# FX_I2C_Proto_Shield_v1_0.net
KiCad netlist of a schematic drawn in EAGLE
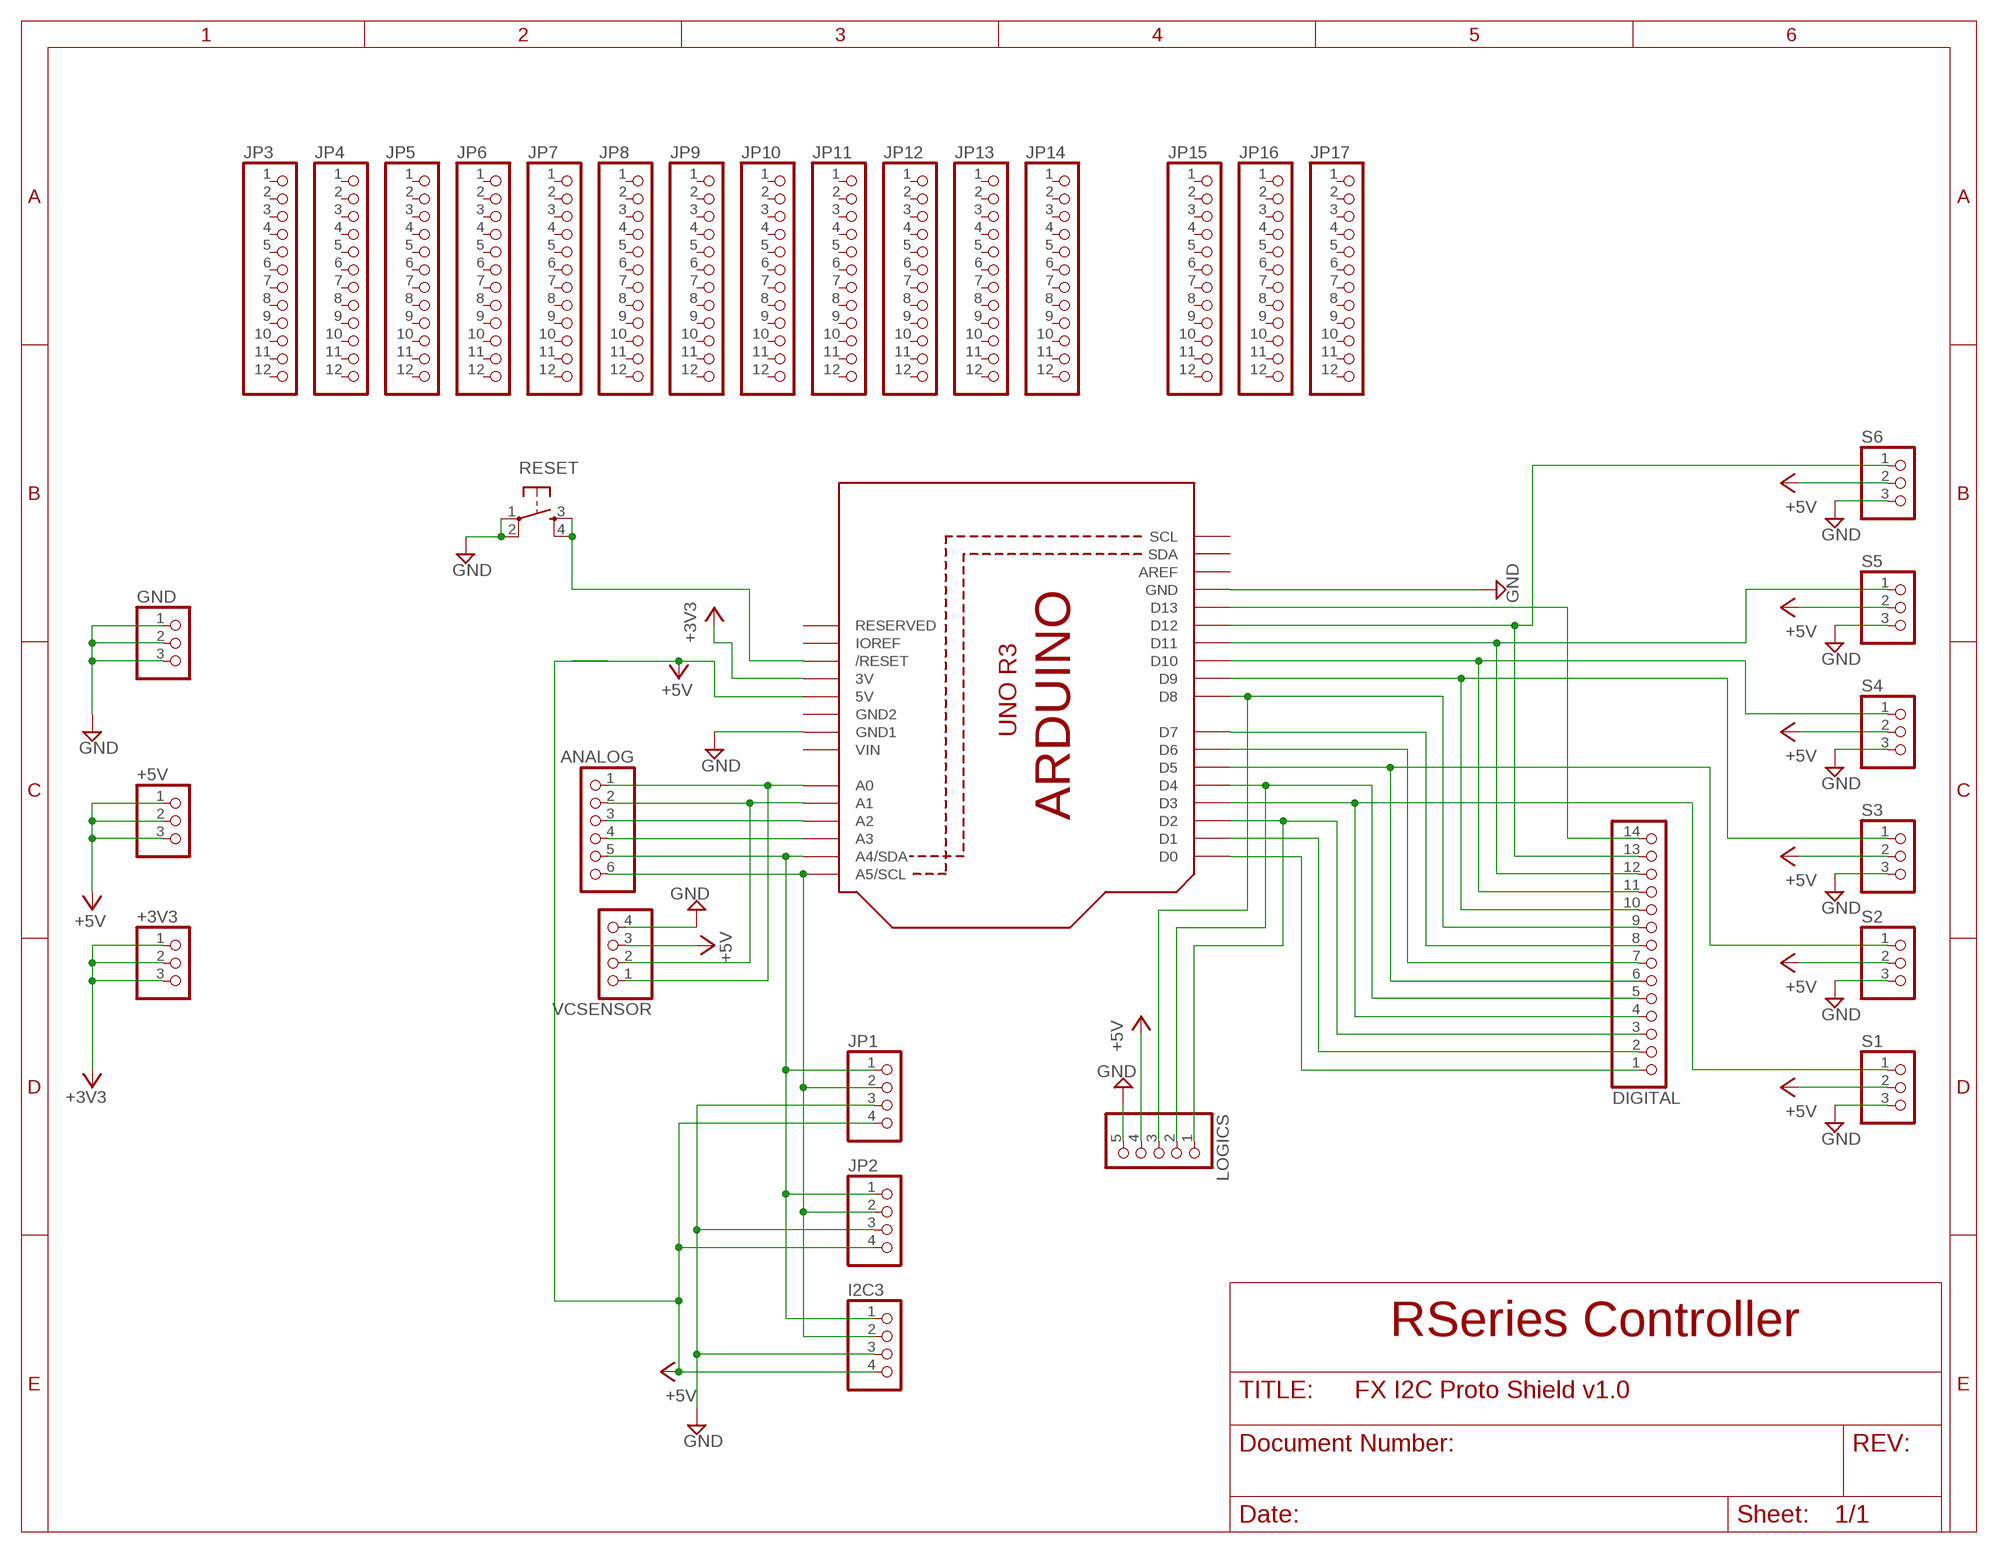
[diagram p0: schematic, sheet 1]

(export (version "E")
  (design (tool "Eeschema 10.0.6"))
  (components
    (comp (ref "+3V3")
      (value "PINHD-1X3CB")
      (footprint "eagle-import:1X03-CLEANBIG")
      (libsource (lib "eagle-import") (part "PINHD-1X3CB"))
    )
    (comp (ref "+5V")
      (value "PINHD-1X3CB")
      (footprint "eagle-import:1X03-CLEANBIG")
      (libsource (lib "eagle-import") (part "PINHD-1X3CB"))
    )
    (comp (ref "ANALOG")
      (value "PINHD-1X6B")
      (footprint "eagle-import:1X06-BIG")
      (libsource (lib "eagle-import") (part "PINHD-1X6B"))
    )
    (comp (ref "DIGITAL")
      (value "PINHD-1X14-CB")
      (footprint "eagle-import:1X14-CB")
      (libsource (lib "eagle-import") (part "PINHD-1X14-CB"))
    )
    (comp (ref "GND")
      (value "PINHD-1X3CB")
      (footprint "eagle-import:1X03-CLEANBIG")
      (libsource (lib "eagle-import") (part "PINHD-1X3CB"))
    )
    (comp (ref "I2C3")
      (value "PINHD-1X4")
      (footprint "eagle-import:1X04")
      (libsource (lib "eagle-import") (part "PINHD-1X4"))
    )
    (comp (ref "JP1")
      (value "PINHD-1X4")
      (footprint "eagle-import:1X04")
      (libsource (lib "eagle-import") (part "PINHD-1X4"))
    )
    (comp (ref "JP2")
      (value "PINHD-1X4")
      (footprint "eagle-import:1X04")
      (libsource (lib "eagle-import") (part "PINHD-1X4"))
    )
    (comp (ref "JP3")
      (value "PINHD-1X12-CB")
      (footprint "eagle-import:1X12-CB")
      (libsource (lib "eagle-import") (part "PINHD-1X12-CB"))
    )
    (comp (ref "JP4")
      (value "PINHD-1X12-CB")
      (footprint "eagle-import:1X12-CB")
      (libsource (lib "eagle-import") (part "PINHD-1X12-CB"))
    )
    (comp (ref "JP5")
      (value "PINHD-1X12-CB")
      (footprint "eagle-import:1X12-CB")
      (libsource (lib "eagle-import") (part "PINHD-1X12-CB"))
    )
    (comp (ref "JP6")
      (value "PINHD-1X12-CB")
      (footprint "eagle-import:1X12-CB")
      (libsource (lib "eagle-import") (part "PINHD-1X12-CB"))
    )
    (comp (ref "JP7")
      (value "PINHD-1X12-CB")
      (footprint "eagle-import:1X12-CB")
      (libsource (lib "eagle-import") (part "PINHD-1X12-CB"))
    )
    (comp (ref "JP8")
      (value "PINHD-1X12-CB")
      (footprint "eagle-import:1X12-CB")
      (libsource (lib "eagle-import") (part "PINHD-1X12-CB"))
    )
    (comp (ref "JP9")
      (value "PINHD-1X12-CB")
      (footprint "eagle-import:1X12-CB")
      (libsource (lib "eagle-import") (part "PINHD-1X12-CB"))
    )
    (comp (ref "JP10")
      (value "PINHD-1X12-CB")
      (footprint "eagle-import:1X12-CB")
      (libsource (lib "eagle-import") (part "PINHD-1X12-CB"))
    )
    (comp (ref "JP11")
      (value "PINHD-1X12-CB")
      (footprint "eagle-import:1X12-CB")
      (libsource (lib "eagle-import") (part "PINHD-1X12-CB"))
    )
    (comp (ref "JP12")
      (value "PINHD-1X12-CB")
      (footprint "eagle-import:1X12-CB")
      (libsource (lib "eagle-import") (part "PINHD-1X12-CB"))
    )
    (comp (ref "JP13")
      (value "PINHD-1X12-CB")
      (footprint "eagle-import:1X12-CB")
      (libsource (lib "eagle-import") (part "PINHD-1X12-CB"))
    )
    (comp (ref "JP14")
      (value "PINHD-1X12-CB")
      (footprint "eagle-import:1X12-CB")
      (libsource (lib "eagle-import") (part "PINHD-1X12-CB"))
    )
    (comp (ref "JP15")
      (value "PINHD-1X12-CB")
      (footprint "eagle-import:1X12-CB")
      (libsource (lib "eagle-import") (part "PINHD-1X12-CB"))
    )
    (comp (ref "JP16")
      (value "PINHD-1X12-CB")
      (footprint "eagle-import:1X12-CB")
      (libsource (lib "eagle-import") (part "PINHD-1X12-CB"))
    )
    (comp (ref "JP17")
      (value "PINHD-1X12-CB")
      (footprint "eagle-import:1X12-CB")
      (libsource (lib "eagle-import") (part "PINHD-1X12-CB"))
    )
    (comp (ref "LOGICS")
      (value "PINHD-1X5")
      (footprint "eagle-import:1X05")
      (libsource (lib "eagle-import") (part "PINHD-1X5"))
    )
    (comp (ref "RESET")
      (value "TAC_SWITCHPTH")
      (footprint "eagle-import:TACTILE-PTH")
      (libsource (lib "eagle-import") (part "TAC_SWITCHPTH"))
    )
    (comp (ref "S1")
      (value "PINHD-1X3")
      (footprint "eagle-import:1X03")
      (libsource (lib "eagle-import") (part "PINHD-1X3"))
    )
    (comp (ref "S2")
      (value "PINHD-1X3")
      (footprint "eagle-import:1X03")
      (libsource (lib "eagle-import") (part "PINHD-1X3"))
    )
    (comp (ref "S3")
      (value "PINHD-1X3")
      (footprint "eagle-import:1X03")
      (libsource (lib "eagle-import") (part "PINHD-1X3"))
    )
    (comp (ref "S4")
      (value "PINHD-1X3")
      (footprint "eagle-import:1X03")
      (libsource (lib "eagle-import") (part "PINHD-1X3"))
    )
    (comp (ref "S5")
      (value "PINHD-1X3")
      (footprint "eagle-import:1X03")
      (libsource (lib "eagle-import") (part "PINHD-1X3"))
    )
    (comp (ref "S6")
      (value "PINHD-1X3")
      (footprint "eagle-import:1X03")
      (libsource (lib "eagle-import") (part "PINHD-1X3"))
    )
    (comp (ref "U1")
      (value "ARDUINOR3-DIMENSION")
      (footprint "eagle-import:ARDUINOR3")
      (libsource (lib "eagle-import") (part "ARDUINOR3-DIMENSION"))
    )
    (comp (ref "VCSENSOR")
      (value "PINHD-1X4")
      (footprint "eagle-import:1X04")
      (libsource (lib "eagle-import") (part "PINHD-1X4"))
    )
  )
  (nets
    (net (code "1") (name "+3V3") (class "Default")
      (node (ref "+3V3") (pin "1") (pinfunction "1_1") (pintype "passive"))
      (node (ref "+3V3") (pin "2") (pinfunction "2_2") (pintype "passive"))
      (node (ref "+3V3") (pin "3") (pinfunction "3_3") (pintype "passive"))
      (node (ref "U1") (pin "3V") (pinfunction "3V_3V") (pintype "power_in"))
    )
    (net (code "2") (name "+5V") (class "Default")
      (node (ref "+5V") (pin "1") (pinfunction "1_1") (pintype "passive"))
      (node (ref "+5V") (pin "2") (pinfunction "2_2") (pintype "passive"))
      (node (ref "+5V") (pin "3") (pinfunction "3_3") (pintype "passive"))
      (node (ref "I2C3") (pin "4") (pinfunction "4_4") (pintype "passive"))
      (node (ref "JP1") (pin "4") (pinfunction "4_4") (pintype "passive"))
      (node (ref "JP2") (pin "4") (pinfunction "4_4") (pintype "passive"))
      (node (ref "LOGICS") (pin "4") (pinfunction "4_4") (pintype "passive"))
      (node (ref "S1") (pin "2") (pinfunction "2_2") (pintype "passive"))
      (node (ref "S2") (pin "2") (pinfunction "2_2") (pintype "passive"))
      (node (ref "S3") (pin "2") (pinfunction "2_2") (pintype "passive"))
      (node (ref "S4") (pin "2") (pinfunction "2_2") (pintype "passive"))
      (node (ref "S5") (pin "2") (pinfunction "2_2") (pintype "passive"))
      (node (ref "S6") (pin "2") (pinfunction "2_2") (pintype "passive"))
      (node (ref "U1") (pin "5V") (pinfunction "5V_5V") (pintype "power_in"))
      (node (ref "VCSENSOR") (pin "3") (pinfunction "3_3") (pintype "passive"))
    )
    (net (code "3") (name "/GND2") (class "Default")
      (node (ref "U1") (pin "GND2") (pinfunction "GND2_GND2") (pintype "power_in"))
    )
    (net (code "4") (name "/VIN") (class "Default")
      (node (ref "U1") (pin "VIN") (pinfunction "VIN_VIN") (pintype "power_in"))
    )
    (net (code "5") (name "GND") (class "Default")
      (node (ref "GND") (pin "1") (pinfunction "1_1") (pintype "passive"))
      (node (ref "GND") (pin "2") (pinfunction "2_2") (pintype "passive"))
      (node (ref "GND") (pin "3") (pinfunction "3_3") (pintype "passive"))
      (node (ref "I2C3") (pin "3") (pinfunction "3_3") (pintype "passive"))
      (node (ref "JP1") (pin "3") (pinfunction "3_3") (pintype "passive"))
      (node (ref "JP2") (pin "3") (pinfunction "3_3") (pintype "passive"))
      (node (ref "LOGICS") (pin "5") (pinfunction "5_5") (pintype "passive"))
      (node (ref "RESET") (pin "1") (pinfunction "1_1") (pintype "passive"))
      (node (ref "RESET") (pin "2") (pinfunction "2_2") (pintype "passive"))
      (node (ref "S1") (pin "3") (pinfunction "3_3") (pintype "passive"))
      (node (ref "S2") (pin "3") (pinfunction "3_3") (pintype "passive"))
      (node (ref "S3") (pin "3") (pinfunction "3_3") (pintype "passive"))
      (node (ref "S4") (pin "3") (pinfunction "3_3") (pintype "passive"))
      (node (ref "S5") (pin "3") (pinfunction "3_3") (pintype "passive"))
      (node (ref "S6") (pin "3") (pinfunction "3_3") (pintype "passive"))
      (node (ref "U1") (pin "GND") (pinfunction "GND_GND") (pintype "power_in"))
      (node (ref "U1") (pin "GND1") (pinfunction "GND1_GND1") (pintype "power_in"))
      (node (ref "VCSENSOR") (pin "4") (pinfunction "4_4") (pintype "passive"))
    )
    (net (code "6") (name "Net-(ANALOG-Pad1)") (class "Default")
      (node (ref "ANALOG") (pin "1") (pinfunction "1_1") (pintype "passive"))
      (node (ref "U1") (pin "A0") (pinfunction "A0_A0") (pintype "bidirectional"))
      (node (ref "VCSENSOR") (pin "1") (pinfunction "1_1") (pintype "passive"))
    )
    (net (code "7") (name "Net-(ANALOG-Pad2)") (class "Default")
      (node (ref "ANALOG") (pin "2") (pinfunction "2_2") (pintype "passive"))
      (node (ref "U1") (pin "A1") (pinfunction "A1_A1") (pintype "bidirectional"))
      (node (ref "VCSENSOR") (pin "2") (pinfunction "2_2") (pintype "passive"))
    )
    (net (code "8") (name "Net-(ANALOG-Pad3)") (class "Default")
      (node (ref "ANALOG") (pin "3") (pinfunction "3_3") (pintype "passive"))
      (node (ref "U1") (pin "A2") (pinfunction "A2_A2") (pintype "bidirectional"))
    )
    (net (code "9") (name "Net-(ANALOG-Pad4)") (class "Default")
      (node (ref "ANALOG") (pin "4") (pinfunction "4_4") (pintype "passive"))
      (node (ref "U1") (pin "A3") (pinfunction "A3_A3") (pintype "bidirectional"))
    )
    (net (code "10") (name "Net-(DIGITAL-Pad1)") (class "Default")
      (node (ref "DIGITAL") (pin "1") (pinfunction "1_1") (pintype "passive"))
      (node (ref "U1") (pin "D0") (pinfunction "D0_D0") (pintype "bidirectional"))
    )
    (net (code "11") (name "Net-(DIGITAL-Pad2)") (class "Default")
      (node (ref "DIGITAL") (pin "2") (pinfunction "2_2") (pintype "passive"))
      (node (ref "U1") (pin "D1") (pinfunction "D1_D1") (pintype "bidirectional"))
    )
    (net (code "12") (name "Net-(DIGITAL-Pad3)") (class "Default")
      (node (ref "DIGITAL") (pin "3") (pinfunction "3_3") (pintype "passive"))
      (node (ref "LOGICS") (pin "1") (pinfunction "1_1") (pintype "passive"))
      (node (ref "U1") (pin "D2") (pinfunction "D2_D2") (pintype "bidirectional"))
    )
    (net (code "13") (name "Net-(DIGITAL-Pad4)") (class "Default")
      (node (ref "DIGITAL") (pin "4") (pinfunction "4_4") (pintype "passive"))
      (node (ref "S1") (pin "1") (pinfunction "1_1") (pintype "passive"))
      (node (ref "U1") (pin "D3") (pinfunction "D3_D3") (pintype "bidirectional"))
    )
    (net (code "14") (name "Net-(DIGITAL-Pad5)") (class "Default")
      (node (ref "DIGITAL") (pin "5") (pinfunction "5_5") (pintype "passive"))
      (node (ref "LOGICS") (pin "2") (pinfunction "2_2") (pintype "passive"))
      (node (ref "U1") (pin "D4") (pinfunction "D4_D4") (pintype "bidirectional"))
    )
    (net (code "15") (name "Net-(DIGITAL-Pad6)") (class "Default")
      (node (ref "DIGITAL") (pin "6") (pinfunction "6_6") (pintype "passive"))
      (node (ref "S2") (pin "1") (pinfunction "1_1") (pintype "passive"))
      (node (ref "U1") (pin "D5") (pinfunction "D5_D5") (pintype "bidirectional"))
    )
    (net (code "16") (name "Net-(DIGITAL-Pad7)") (class "Default")
      (node (ref "DIGITAL") (pin "7") (pinfunction "7_7") (pintype "passive"))
      (node (ref "U1") (pin "D6") (pinfunction "D6_D6") (pintype "bidirectional"))
    )
    (net (code "17") (name "Net-(DIGITAL-Pad8)") (class "Default")
      (node (ref "DIGITAL") (pin "8") (pinfunction "8_8") (pintype "passive"))
      (node (ref "U1") (pin "D7") (pinfunction "D7_D7") (pintype "bidirectional"))
    )
    (net (code "18") (name "Net-(DIGITAL-Pad9)") (class "Default")
      (node (ref "DIGITAL") (pin "9") (pinfunction "9_9") (pintype "passive"))
      (node (ref "LOGICS") (pin "3") (pinfunction "3_3") (pintype "passive"))
      (node (ref "U1") (pin "D8") (pinfunction "D8_D8") (pintype "bidirectional"))
    )
    (net (code "19") (name "Net-(DIGITAL-Pad10)") (class "Default")
      (node (ref "DIGITAL") (pin "10") (pinfunction "10_10") (pintype "passive"))
      (node (ref "S3") (pin "1") (pinfunction "1_1") (pintype "passive"))
      (node (ref "U1") (pin "D9") (pinfunction "D9_D9") (pintype "bidirectional"))
    )
    (net (code "20") (name "Net-(DIGITAL-Pad11)") (class "Default")
      (node (ref "DIGITAL") (pin "11") (pinfunction "11_11") (pintype "passive"))
      (node (ref "S4") (pin "1") (pinfunction "1_1") (pintype "passive"))
      (node (ref "U1") (pin "D10") (pinfunction "D10_D10") (pintype "bidirectional"))
    )
    (net (code "21") (name "Net-(DIGITAL-Pad12)") (class "Default")
      (node (ref "DIGITAL") (pin "12") (pinfunction "12_12") (pintype "passive"))
      (node (ref "S5") (pin "1") (pinfunction "1_1") (pintype "passive"))
      (node (ref "U1") (pin "D11") (pinfunction "D11_D11") (pintype "bidirectional"))
    )
    (net (code "22") (name "Net-(DIGITAL-Pad13)") (class "Default")
      (node (ref "DIGITAL") (pin "13") (pinfunction "13_13") (pintype "passive"))
      (node (ref "S6") (pin "1") (pinfunction "1_1") (pintype "passive"))
      (node (ref "U1") (pin "D12") (pinfunction "D12_D12") (pintype "bidirectional"))
    )
    (net (code "23") (name "Net-(DIGITAL-Pad14)") (class "Default")
      (node (ref "DIGITAL") (pin "14") (pinfunction "14_14") (pintype "passive"))
      (node (ref "U1") (pin "D13") (pinfunction "D13_D13") (pintype "bidirectional"))
    )
    (net (code "24") (name "Net-(U1-A4{slash}SDA)") (class "Default")
      (node (ref "ANALOG") (pin "5") (pinfunction "5_5") (pintype "passive"))
      (node (ref "I2C3") (pin "1") (pinfunction "1_1") (pintype "passive"))
      (node (ref "JP1") (pin "1") (pinfunction "1_1") (pintype "passive"))
      (node (ref "JP2") (pin "1") (pinfunction "1_1") (pintype "passive"))
      (node (ref "U1") (pin "A4") (pinfunction "A4/SDA_A4") (pintype "bidirectional"))
    )
    (net (code "25") (name "Net-(U1-A5{slash}SCL)") (class "Default")
      (node (ref "ANALOG") (pin "6") (pinfunction "6_6") (pintype "passive"))
      (node (ref "I2C3") (pin "2") (pinfunction "2_2") (pintype "passive"))
      (node (ref "JP1") (pin "2") (pinfunction "2_2") (pintype "passive"))
      (node (ref "JP2") (pin "2") (pinfunction "2_2") (pintype "passive"))
      (node (ref "U1") (pin "A5") (pinfunction "A5/SCL_A5") (pintype "bidirectional"))
    )
    (net (code "26") (name "Net-(U1-{slash}RESET)") (class "Default")
      (node (ref "RESET") (pin "3") (pinfunction "3_3") (pintype "passive"))
      (node (ref "RESET") (pin "4") (pinfunction "4_4") (pintype "passive"))
      (node (ref "U1") (pin "RESET") (pinfunction "/RESET_RESET") (pintype "bidirectional"))
    )
    (net (code "27") (name "unconnected-(JP3-Pad1)") (class "Default")
      (node (ref "JP3") (pin "1") (pinfunction "1_1") (pintype "passive"))
    )
    (net (code "28") (name "unconnected-(JP3-Pad2)") (class "Default")
      (node (ref "JP3") (pin "2") (pinfunction "2_2") (pintype "passive"))
    )
    (net (code "29") (name "unconnected-(JP3-Pad3)") (class "Default")
      (node (ref "JP3") (pin "3") (pinfunction "3_3") (pintype "passive"))
    )
    (net (code "30") (name "unconnected-(JP3-Pad4)") (class "Default")
      (node (ref "JP3") (pin "4") (pinfunction "4_4") (pintype "passive"))
    )
    (net (code "31") (name "unconnected-(JP3-Pad5)") (class "Default")
      (node (ref "JP3") (pin "5") (pinfunction "5_5") (pintype "passive"))
    )
    (net (code "32") (name "unconnected-(JP3-Pad6)") (class "Default")
      (node (ref "JP3") (pin "6") (pinfunction "6_6") (pintype "passive"))
    )
    (net (code "33") (name "unconnected-(JP3-Pad7)") (class "Default")
      (node (ref "JP3") (pin "7") (pinfunction "7_7") (pintype "passive"))
    )
    (net (code "34") (name "unconnected-(JP3-Pad8)") (class "Default")
      (node (ref "JP3") (pin "8") (pinfunction "8_8") (pintype "passive"))
    )
    (net (code "35") (name "unconnected-(JP3-Pad9)") (class "Default")
      (node (ref "JP3") (pin "9") (pinfunction "9_9") (pintype "passive"))
    )
    (net (code "36") (name "unconnected-(JP3-Pad10)") (class "Default")
      (node (ref "JP3") (pin "10") (pinfunction "10_10") (pintype "passive"))
    )
    (net (code "37") (name "unconnected-(JP3-Pad11)") (class "Default")
      (node (ref "JP3") (pin "11") (pinfunction "11_11") (pintype "passive"))
    )
    (net (code "38") (name "unconnected-(JP3-Pad12)") (class "Default")
      (node (ref "JP3") (pin "12") (pinfunction "12_12") (pintype "passive"))
    )
    (net (code "39") (name "unconnected-(JP4-Pad1)") (class "Default")
      (node (ref "JP4") (pin "1") (pinfunction "1_1") (pintype "passive"))
    )
    (net (code "40") (name "unconnected-(JP4-Pad2)") (class "Default")
      (node (ref "JP4") (pin "2") (pinfunction "2_2") (pintype "passive"))
    )
    (net (code "41") (name "unconnected-(JP4-Pad3)") (class "Default")
      (node (ref "JP4") (pin "3") (pinfunction "3_3") (pintype "passive"))
    )
    (net (code "42") (name "unconnected-(JP4-Pad4)") (class "Default")
      (node (ref "JP4") (pin "4") (pinfunction "4_4") (pintype "passive"))
    )
    (net (code "43") (name "unconnected-(JP4-Pad5)") (class "Default")
      (node (ref "JP4") (pin "5") (pinfunction "5_5") (pintype "passive"))
    )
    (net (code "44") (name "unconnected-(JP4-Pad6)") (class "Default")
      (node (ref "JP4") (pin "6") (pinfunction "6_6") (pintype "passive"))
    )
    (net (code "45") (name "unconnected-(JP4-Pad7)") (class "Default")
      (node (ref "JP4") (pin "7") (pinfunction "7_7") (pintype "passive"))
    )
    (net (code "46") (name "unconnected-(JP4-Pad8)") (class "Default")
      (node (ref "JP4") (pin "8") (pinfunction "8_8") (pintype "passive"))
    )
    (net (code "47") (name "unconnected-(JP4-Pad9)") (class "Default")
      (node (ref "JP4") (pin "9") (pinfunction "9_9") (pintype "passive"))
    )
    (net (code "48") (name "unconnected-(JP4-Pad10)") (class "Default")
      (node (ref "JP4") (pin "10") (pinfunction "10_10") (pintype "passive"))
    )
    (net (code "49") (name "unconnected-(JP4-Pad11)") (class "Default")
      (node (ref "JP4") (pin "11") (pinfunction "11_11") (pintype "passive"))
    )
    (net (code "50") (name "unconnected-(JP4-Pad12)") (class "Default")
      (node (ref "JP4") (pin "12") (pinfunction "12_12") (pintype "passive"))
    )
    (net (code "51") (name "unconnected-(JP5-Pad1)") (class "Default")
      (node (ref "JP5") (pin "1") (pinfunction "1_1") (pintype "passive"))
    )
    (net (code "52") (name "unconnected-(JP5-Pad2)") (class "Default")
      (node (ref "JP5") (pin "2") (pinfunction "2_2") (pintype "passive"))
    )
    (net (code "53") (name "unconnected-(JP5-Pad3)") (class "Default")
      (node (ref "JP5") (pin "3") (pinfunction "3_3") (pintype "passive"))
    )
    (net (code "54") (name "unconnected-(JP5-Pad4)") (class "Default")
      (node (ref "JP5") (pin "4") (pinfunction "4_4") (pintype "passive"))
    )
    (net (code "55") (name "unconnected-(JP5-Pad5)") (class "Default")
      (node (ref "JP5") (pin "5") (pinfunction "5_5") (pintype "passive"))
    )
    (net (code "56") (name "unconnected-(JP5-Pad6)") (class "Default")
      (node (ref "JP5") (pin "6") (pinfunction "6_6") (pintype "passive"))
    )
    (net (code "57") (name "unconnected-(JP5-Pad7)") (class "Default")
      (node (ref "JP5") (pin "7") (pinfunction "7_7") (pintype "passive"))
    )
    (net (code "58") (name "unconnected-(JP5-Pad8)") (class "Default")
      (node (ref "JP5") (pin "8") (pinfunction "8_8") (pintype "passive"))
    )
    (net (code "59") (name "unconnected-(JP5-Pad9)") (class "Default")
      (node (ref "JP5") (pin "9") (pinfunction "9_9") (pintype "passive"))
    )
    (net (code "60") (name "unconnected-(JP5-Pad10)") (class "Default")
      (node (ref "JP5") (pin "10") (pinfunction "10_10") (pintype "passive"))
    )
    (net (code "61") (name "unconnected-(JP5-Pad11)") (class "Default")
      (node (ref "JP5") (pin "11") (pinfunction "11_11") (pintype "passive"))
    )
    (net (code "62") (name "unconnected-(JP5-Pad12)") (class "Default")
      (node (ref "JP5") (pin "12") (pinfunction "12_12") (pintype "passive"))
    )
    (net (code "63") (name "unconnected-(JP6-Pad1)") (class "Default")
      (node (ref "JP6") (pin "1") (pinfunction "1_1") (pintype "passive"))
    )
    (net (code "64") (name "unconnected-(JP6-Pad2)") (class "Default")
      (node (ref "JP6") (pin "2") (pinfunction "2_2") (pintype "passive"))
    )
    (net (code "65") (name "unconnected-(JP6-Pad3)") (class "Default")
      (node (ref "JP6") (pin "3") (pinfunction "3_3") (pintype "passive"))
    )
    (net (code "66") (name "unconnected-(JP6-Pad4)") (class "Default")
      (node (ref "JP6") (pin "4") (pinfunction "4_4") (pintype "passive"))
    )
    (net (code "67") (name "unconnected-(JP6-Pad5)") (class "Default")
      (node (ref "JP6") (pin "5") (pinfunction "5_5") (pintype "passive"))
    )
    (net (code "68") (name "unconnected-(JP6-Pad6)") (class "Default")
      (node (ref "JP6") (pin "6") (pinfunction "6_6") (pintype "passive"))
    )
    (net (code "69") (name "unconnected-(JP6-Pad7)") (class "Default")
      (node (ref "JP6") (pin "7") (pinfunction "7_7") (pintype "passive"))
    )
    (net (code "70") (name "unconnected-(JP6-Pad8)") (class "Default")
      (node (ref "JP6") (pin "8") (pinfunction "8_8") (pintype "passive"))
    )
    (net (code "71") (name "unconnected-(JP6-Pad9)") (class "Default")
      (node (ref "JP6") (pin "9") (pinfunction "9_9") (pintype "passive"))
    )
    (net (code "72") (name "unconnected-(JP6-Pad10)") (class "Default")
      (node (ref "JP6") (pin "10") (pinfunction "10_10") (pintype "passive"))
    )
    (net (code "73") (name "unconnected-(JP6-Pad11)") (class "Default")
      (node (ref "JP6") (pin "11") (pinfunction "11_11") (pintype "passive"))
    )
    (net (code "74") (name "unconnected-(JP6-Pad12)") (class "Default")
      (node (ref "JP6") (pin "12") (pinfunction "12_12") (pintype "passive"))
    )
    (net (code "75") (name "unconnected-(JP7-Pad1)") (class "Default")
      (node (ref "JP7") (pin "1") (pinfunction "1_1") (pintype "passive"))
    )
    (net (code "76") (name "unconnected-(JP7-Pad2)") (class "Default")
      (node (ref "JP7") (pin "2") (pinfunction "2_2") (pintype "passive"))
    )
    (net (code "77") (name "unconnected-(JP7-Pad3)") (class "Default")
      (node (ref "JP7") (pin "3") (pinfunction "3_3") (pintype "passive"))
    )
    (net (code "78") (name "unconnected-(JP7-Pad4)") (class "Default")
      (node (ref "JP7") (pin "4") (pinfunction "4_4") (pintype "passive"))
    )
    (net (code "79") (name "unconnected-(JP7-Pad5)") (class "Default")
      (node (ref "JP7") (pin "5") (pinfunction "5_5") (pintype "passive"))
    )
    (net (code "80") (name "unconnected-(JP7-Pad6)") (class "Default")
      (node (ref "JP7") (pin "6") (pinfunction "6_6") (pintype "passive"))
    )
    (net (code "81") (name "unconnected-(JP7-Pad7)") (class "Default")
      (node (ref "JP7") (pin "7") (pinfunction "7_7") (pintype "passive"))
    )
    (net (code "82") (name "unconnected-(JP7-Pad8)") (class "Default")
      (node (ref "JP7") (pin "8") (pinfunction "8_8") (pintype "passive"))
    )
    (net (code "83") (name "unconnected-(JP7-Pad9)") (class "Default")
      (node (ref "JP7") (pin "9") (pinfunction "9_9") (pintype "passive"))
    )
    (net (code "84") (name "unconnected-(JP7-Pad10)") (class "Default")
      (node (ref "JP7") (pin "10") (pinfunction "10_10") (pintype "passive"))
    )
    (net (code "85") (name "unconnected-(JP7-Pad11)") (class "Default")
      (node (ref "JP7") (pin "11") (pinfunction "11_11") (pintype "passive"))
    )
    (net (code "86") (name "unconnected-(JP7-Pad12)") (class "Default")
      (node (ref "JP7") (pin "12") (pinfunction "12_12") (pintype "passive"))
    )
    (net (code "87") (name "unconnected-(JP8-Pad1)") (class "Default")
      (node (ref "JP8") (pin "1") (pinfunction "1_1") (pintype "passive"))
    )
    (net (code "88") (name "unconnected-(JP8-Pad2)") (class "Default")
      (node (ref "JP8") (pin "2") (pinfunction "2_2") (pintype "passive"))
    )
    (net (code "89") (name "unconnected-(JP8-Pad3)") (class "Default")
      (node (ref "JP8") (pin "3") (pinfunction "3_3") (pintype "passive"))
    )
    (net (code "90") (name "unconnected-(JP8-Pad4)") (class "Default")
      (node (ref "JP8") (pin "4") (pinfunction "4_4") (pintype "passive"))
    )
    (net (code "91") (name "unconnected-(JP8-Pad5)") (class "Default")
      (node (ref "JP8") (pin "5") (pinfunction "5_5") (pintype "passive"))
    )
    (net (code "92") (name "unconnected-(JP8-Pad6)") (class "Default")
      (node (ref "JP8") (pin "6") (pinfunction "6_6") (pintype "passive"))
    )
    (net (code "93") (name "unconnected-(JP8-Pad7)") (class "Default")
      (node (ref "JP8") (pin "7") (pinfunction "7_7") (pintype "passive"))
    )
    (net (code "94") (name "unconnected-(JP8-Pad8)") (class "Default")
      (node (ref "JP8") (pin "8") (pinfunction "8_8") (pintype "passive"))
    )
    (net (code "95") (name "unconnected-(JP8-Pad9)") (class "Default")
      (node (ref "JP8") (pin "9") (pinfunction "9_9") (pintype "passive"))
    )
    (net (code "96") (name "unconnected-(JP8-Pad10)") (class "Default")
      (node (ref "JP8") (pin "10") (pinfunction "10_10") (pintype "passive"))
    )
    (net (code "97") (name "unconnected-(JP8-Pad11)") (class "Default")
      (node (ref "JP8") (pin "11") (pinfunction "11_11") (pintype "passive"))
    )
    (net (code "98") (name "unconnected-(JP8-Pad12)") (class "Default")
      (node (ref "JP8") (pin "12") (pinfunction "12_12") (pintype "passive"))
    )
    (net (code "99") (name "unconnected-(JP9-Pad1)") (class "Default")
      (node (ref "JP9") (pin "1") (pinfunction "1_1") (pintype "passive"))
    )
    (net (code "100") (name "unconnected-(JP9-Pad2)") (class "Default")
      (node (ref "JP9") (pin "2") (pinfunction "2_2") (pintype "passive"))
    )
    (net (code "101") (name "unconnected-(JP9-Pad3)") (class "Default")
      (node (ref "JP9") (pin "3") (pinfunction "3_3") (pintype "passive"))
    )
    (net (code "102") (name "unconnected-(JP9-Pad4)") (class "Default")
      (node (ref "JP9") (pin "4") (pinfunction "4_4") (pintype "passive"))
    )
    (net (code "103") (name "unconnected-(JP9-Pad5)") (class "Default")
      (node (ref "JP9") (pin "5") (pinfunction "5_5") (pintype "passive"))
    )
    (net (code "104") (name "unconnected-(JP9-Pad6)") (class "Default")
      (node (ref "JP9") (pin "6") (pinfunction "6_6") (pintype "passive"))
    )
    (net (code "105") (name "unconnected-(JP9-Pad7)") (class "Default")
      (node (ref "JP9") (pin "7") (pinfunction "7_7") (pintype "passive"))
    )
    (net (code "106") (name "unconnected-(JP9-Pad8)") (class "Default")
      (node (ref "JP9") (pin "8") (pinfunction "8_8") (pintype "passive"))
    )
    (net (code "107") (name "unconnected-(JP9-Pad9)") (class "Default")
      (node (ref "JP9") (pin "9") (pinfunction "9_9") (pintype "passive"))
    )
    (net (code "108") (name "unconnected-(JP9-Pad10)") (class "Default")
      (node (ref "JP9") (pin "10") (pinfunction "10_10") (pintype "passive"))
    )
    (net (code "109") (name "unconnected-(JP9-Pad11)") (class "Default")
      (node (ref "JP9") (pin "11") (pinfunction "11_11") (pintype "passive"))
    )
    (net (code "110") (name "unconnected-(JP9-Pad12)") (class "Default")
      (node (ref "JP9") (pin "12") (pinfunction "12_12") (pintype "passive"))
    )
    (net (code "111") (name "unconnected-(JP10-Pad1)") (class "Default")
      (node (ref "JP10") (pin "1") (pinfunction "1_1") (pintype "passive"))
    )
    (net (code "112") (name "unconnected-(JP10-Pad2)") (class "Default")
      (node (ref "JP10") (pin "2") (pinfunction "2_2") (pintype "passive"))
    )
    (net (code "113") (name "unconnected-(JP10-Pad3)") (class "Default")
      (node (ref "JP10") (pin "3") (pinfunction "3_3") (pintype "passive"))
    )
    (net (code "114") (name "unconnected-(JP10-Pad4)") (class "Default")
      (node (ref "JP10") (pin "4") (pinfunction "4_4") (pintype "passive"))
    )
    (net (code "115") (name "unconnected-(JP10-Pad5)") (class "Default")
      (node (ref "JP10") (pin "5") (pinfunction "5_5") (pintype "passive"))
    )
    (net (code "116") (name "unconnected-(JP10-Pad6)") (class "Default")
      (node (ref "JP10") (pin "6") (pinfunction "6_6") (pintype "passive"))
    )
    (net (code "117") (name "unconnected-(JP10-Pad7)") (class "Default")
      (node (ref "JP10") (pin "7") (pinfunction "7_7") (pintype "passive"))
    )
    (net (code "118") (name "unconnected-(JP10-Pad8)") (class "Default")
      (node (ref "JP10") (pin "8") (pinfunction "8_8") (pintype "passive"))
    )
    (net (code "119") (name "unconnected-(JP10-Pad9)") (class "Default")
      (node (ref "JP10") (pin "9") (pinfunction "9_9") (pintype "passive"))
    )
    (net (code "120") (name "unconnected-(JP10-Pad10)") (class "Default")
      (node (ref "JP10") (pin "10") (pinfunction "10_10") (pintype "passive"))
    )
    (net (code "121") (name "unconnected-(JP10-Pad11)") (class "Default")
      (node (ref "JP10") (pin "11") (pinfunction "11_11") (pintype "passive"))
    )
    (net (code "122") (name "unconnected-(JP10-Pad12)") (class "Default")
      (node (ref "JP10") (pin "12") (pinfunction "12_12") (pintype "passive"))
    )
    (net (code "123") (name "unconnected-(JP11-Pad1)") (class "Default")
      (node (ref "JP11") (pin "1") (pinfunction "1_1") (pintype "passive"))
    )
    (net (code "124") (name "unconnected-(JP11-Pad2)") (class "Default")
      (node (ref "JP11") (pin "2") (pinfunction "2_2") (pintype "passive"))
    )
    (net (code "125") (name "unconnected-(JP11-Pad3)") (class "Default")
      (node (ref "JP11") (pin "3") (pinfunction "3_3") (pintype "passive"))
    )
    (net (code "126") (name "unconnected-(JP11-Pad4)") (class "Default")
      (node (ref "JP11") (pin "4") (pinfunction "4_4") (pintype "passive"))
    )
    (net (code "127") (name "unconnected-(JP11-Pad5)") (class "Default")
      (node (ref "JP11") (pin "5") (pinfunction "5_5") (pintype "passive"))
    )
    (net (code "128") (name "unconnected-(JP11-Pad6)") (class "Default")
      (node (ref "JP11") (pin "6") (pinfunction "6_6") (pintype "passive"))
    )
    (net (code "129") (name "unconnected-(JP11-Pad7)") (class "Default")
      (node (ref "JP11") (pin "7") (pinfunction "7_7") (pintype "passive"))
    )
    (net (code "130") (name "unconnected-(JP11-Pad8)") (class "Default")
      (node (ref "JP11") (pin "8") (pinfunction "8_8") (pintype "passive"))
    )
    (net (code "131") (name "unconnected-(JP11-Pad9)") (class "Default")
      (node (ref "JP11") (pin "9") (pinfunction "9_9") (pintype "passive"))
    )
    (net (code "132") (name "unconnected-(JP11-Pad10)") (class "Default")
      (node (ref "JP11") (pin "10") (pinfunction "10_10") (pintype "passive"))
    )
    (net (code "133") (name "unconnected-(JP11-Pad11)") (class "Default")
      (node (ref "JP11") (pin "11") (pinfunction "11_11") (pintype "passive"))
    )
    (net (code "134") (name "unconnected-(JP11-Pad12)") (class "Default")
      (node (ref "JP11") (pin "12") (pinfunction "12_12") (pintype "passive"))
    )
    (net (code "135") (name "unconnected-(JP12-Pad1)") (class "Default")
      (node (ref "JP12") (pin "1") (pinfunction "1_1") (pintype "passive"))
    )
    (net (code "136") (name "unconnected-(JP12-Pad2)") (class "Default")
      (node (ref "JP12") (pin "2") (pinfunction "2_2") (pintype "passive"))
    )
    (net (code "137") (name "unconnected-(JP12-Pad3)") (class "Default")
      (node (ref "JP12") (pin "3") (pinfunction "3_3") (pintype "passive"))
    )
    (net (code "138") (name "unconnected-(JP12-Pad4)") (class "Default")
      (node (ref "JP12") (pin "4") (pinfunction "4_4") (pintype "passive"))
    )
    (net (code "139") (name "unconnected-(JP12-Pad5)") (class "Default")
      (node (ref "JP12") (pin "5") (pinfunction "5_5") (pintype "passive"))
    )
    (net (code "140") (name "unconnected-(JP12-Pad6)") (class "Default")
      (node (ref "JP12") (pin "6") (pinfunction "6_6") (pintype "passive"))
    )
    (net (code "141") (name "unconnected-(JP12-Pad7)") (class "Default")
      (node (ref "JP12") (pin "7") (pinfunction "7_7") (pintype "passive"))
    )
    (net (code "142") (name "unconnected-(JP12-Pad8)") (class "Default")
      (node (ref "JP12") (pin "8") (pinfunction "8_8") (pintype "passive"))
    )
    (net (code "143") (name "unconnected-(JP12-Pad9)") (class "Default")
      (node (ref "JP12") (pin "9") (pinfunction "9_9") (pintype "passive"))
    )
    (net (code "144") (name "unconnected-(JP12-Pad10)") (class "Default")
      (node (ref "JP12") (pin "10") (pinfunction "10_10") (pintype "passive"))
    )
    (net (code "145") (name "unconnected-(JP12-Pad11)") (class "Default")
      (node (ref "JP12") (pin "11") (pinfunction "11_11") (pintype "passive"))
    )
    (net (code "146") (name "unconnected-(JP12-Pad12)") (class "Default")
      (node (ref "JP12") (pin "12") (pinfunction "12_12") (pintype "passive"))
    )
    (net (code "147") (name "unconnected-(JP13-Pad1)") (class "Default")
      (node (ref "JP13") (pin "1") (pinfunction "1_1") (pintype "passive"))
    )
    (net (code "148") (name "unconnected-(JP13-Pad2)") (class "Default")
      (node (ref "JP13") (pin "2") (pinfunction "2_2") (pintype "passive"))
    )
    (net (code "149") (name "unconnected-(JP13-Pad3)") (class "Default")
      (node (ref "JP13") (pin "3") (pinfunction "3_3") (pintype "passive"))
    )
    (net (code "150") (name "unconnected-(JP13-Pad4)") (class "Default")
      (node (ref "JP13") (pin "4") (pinfunction "4_4") (pintype "passive"))
    )
    (net (code "151") (name "unconnected-(JP13-Pad5)") (class "Default")
      (node (ref "JP13") (pin "5") (pinfunction "5_5") (pintype "passive"))
    )
    (net (code "152") (name "unconnected-(JP13-Pad6)") (class "Default")
      (node (ref "JP13") (pin "6") (pinfunction "6_6") (pintype "passive"))
    )
    (net (code "153") (name "unconnected-(JP13-Pad7)") (class "Default")
      (node (ref "JP13") (pin "7") (pinfunction "7_7") (pintype "passive"))
    )
    (net (code "154") (name "unconnected-(JP13-Pad8)") (class "Default")
      (node (ref "JP13") (pin "8") (pinfunction "8_8") (pintype "passive"))
    )
    (net (code "155") (name "unconnected-(JP13-Pad9)") (class "Default")
      (node (ref "JP13") (pin "9") (pinfunction "9_9") (pintype "passive"))
    )
    (net (code "156") (name "unconnected-(JP13-Pad10)") (class "Default")
      (node (ref "JP13") (pin "10") (pinfunction "10_10") (pintype "passive"))
    )
    (net (code "157") (name "unconnected-(JP13-Pad11)") (class "Default")
      (node (ref "JP13") (pin "11") (pinfunction "11_11") (pintype "passive"))
    )
    (net (code "158") (name "unconnected-(JP13-Pad12)") (class "Default")
      (node (ref "JP13") (pin "12") (pinfunction "12_12") (pintype "passive"))
    )
    (net (code "159") (name "unconnected-(JP14-Pad1)") (class "Default")
      (node (ref "JP14") (pin "1") (pinfunction "1_1") (pintype "passive"))
    )
    (net (code "160") (name "unconnected-(JP14-Pad2)") (class "Default")
      (node (ref "JP14") (pin "2") (pinfunction "2_2") (pintype "passive"))
    )
    (net (code "161") (name "unconnected-(JP14-Pad3)") (class "Default")
      (node (ref "JP14") (pin "3") (pinfunction "3_3") (pintype "passive"))
    )
    (net (code "162") (name "unconnected-(JP14-Pad4)") (class "Default")
      (node (ref "JP14") (pin "4") (pinfunction "4_4") (pintype "passive"))
    )
    (net (code "163") (name "unconnected-(JP14-Pad5)") (class "Default")
      (node (ref "JP14") (pin "5") (pinfunction "5_5") (pintype "passive"))
    )
    (net (code "164") (name "unconnected-(JP14-Pad6)") (class "Default")
      (node (ref "JP14") (pin "6") (pinfunction "6_6") (pintype "passive"))
    )
    (net (code "165") (name "unconnected-(JP14-Pad7)") (class "Default")
      (node (ref "JP14") (pin "7") (pinfunction "7_7") (pintype "passive"))
    )
    (net (code "166") (name "unconnected-(JP14-Pad8)") (class "Default")
      (node (ref "JP14") (pin "8") (pinfunction "8_8") (pintype "passive"))
    )
    (net (code "167") (name "unconnected-(JP14-Pad9)") (class "Default")
      (node (ref "JP14") (pin "9") (pinfunction "9_9") (pintype "passive"))
    )
    (net (code "168") (name "unconnected-(JP14-Pad10)") (class "Default")
      (node (ref "JP14") (pin "10") (pinfunction "10_10") (pintype "passive"))
    )
    (net (code "169") (name "unconnected-(JP14-Pad11)") (class "Default")
      (node (ref "JP14") (pin "11") (pinfunction "11_11") (pintype "passive"))
    )
    (net (code "170") (name "unconnected-(JP14-Pad12)") (class "Default")
      (node (ref "JP14") (pin "12") (pinfunction "12_12") (pintype "passive"))
    )
    (net (code "171") (name "unconnected-(JP15-Pad1)") (class "Default")
      (node (ref "JP15") (pin "1") (pinfunction "1_1") (pintype "passive"))
    )
    (net (code "172") (name "unconnected-(JP15-Pad2)") (class "Default")
      (node (ref "JP15") (pin "2") (pinfunction "2_2") (pintype "passive"))
    )
    (net (code "173") (name "unconnected-(JP15-Pad3)") (class "Default")
      (node (ref "JP15") (pin "3") (pinfunction "3_3") (pintype "passive"))
    )
    (net (code "174") (name "unconnected-(JP15-Pad4)") (class "Default")
      (node (ref "JP15") (pin "4") (pinfunction "4_4") (pintype "passive"))
    )
    (net (code "175") (name "unconnected-(JP15-Pad5)") (class "Default")
      (node (ref "JP15") (pin "5") (pinfunction "5_5") (pintype "passive"))
    )
    (net (code "176") (name "unconnected-(JP15-Pad6)") (class "Default")
      (node (ref "JP15") (pin "6") (pinfunction "6_6") (pintype "passive"))
    )
    (net (code "177") (name "unconnected-(JP15-Pad7)") (class "Default")
      (node (ref "JP15") (pin "7") (pinfunction "7_7") (pintype "passive"))
    )
    (net (code "178") (name "unconnected-(JP15-Pad8)") (class "Default")
      (node (ref "JP15") (pin "8") (pinfunction "8_8") (pintype "passive"))
    )
    (net (code "179") (name "unconnected-(JP15-Pad9)") (class "Default")
      (node (ref "JP15") (pin "9") (pinfunction "9_9") (pintype "passive"))
    )
    (net (code "180") (name "unconnected-(JP15-Pad10)") (class "Default")
      (node (ref "JP15") (pin "10") (pinfunction "10_10") (pintype "passive"))
    )
    (net (code "181") (name "unconnected-(JP15-Pad11)") (class "Default")
      (node (ref "JP15") (pin "11") (pinfunction "11_11") (pintype "passive"))
    )
    (net (code "182") (name "unconnected-(JP15-Pad12)") (class "Default")
      (node (ref "JP15") (pin "12") (pinfunction "12_12") (pintype "passive"))
    )
    (net (code "183") (name "unconnected-(JP16-Pad1)") (class "Default")
      (node (ref "JP16") (pin "1") (pinfunction "1_1") (pintype "passive"))
    )
    (net (code "184") (name "unconnected-(JP16-Pad2)") (class "Default")
      (node (ref "JP16") (pin "2") (pinfunction "2_2") (pintype "passive"))
    )
    (net (code "185") (name "unconnected-(JP16-Pad3)") (class "Default")
      (node (ref "JP16") (pin "3") (pinfunction "3_3") (pintype "passive"))
    )
    (net (code "186") (name "unconnected-(JP16-Pad4)") (class "Default")
      (node (ref "JP16") (pin "4") (pinfunction "4_4") (pintype "passive"))
    )
    (net (code "187") (name "unconnected-(JP16-Pad5)") (class "Default")
      (node (ref "JP16") (pin "5") (pinfunction "5_5") (pintype "passive"))
    )
    (net (code "188") (name "unconnected-(JP16-Pad6)") (class "Default")
      (node (ref "JP16") (pin "6") (pinfunction "6_6") (pintype "passive"))
    )
    (net (code "189") (name "unconnected-(JP16-Pad7)") (class "Default")
      (node (ref "JP16") (pin "7") (pinfunction "7_7") (pintype "passive"))
    )
    (net (code "190") (name "unconnected-(JP16-Pad8)") (class "Default")
      (node (ref "JP16") (pin "8") (pinfunction "8_8") (pintype "passive"))
    )
    (net (code "191") (name "unconnected-(JP16-Pad9)") (class "Default")
      (node (ref "JP16") (pin "9") (pinfunction "9_9") (pintype "passive"))
    )
    (net (code "192") (name "unconnected-(JP16-Pad10)") (class "Default")
      (node (ref "JP16") (pin "10") (pinfunction "10_10") (pintype "passive"))
    )
    (net (code "193") (name "unconnected-(JP16-Pad11)") (class "Default")
      (node (ref "JP16") (pin "11") (pinfunction "11_11") (pintype "passive"))
    )
    (net (code "194") (name "unconnected-(JP16-Pad12)") (class "Default")
      (node (ref "JP16") (pin "12") (pinfunction "12_12") (pintype "passive"))
    )
    (net (code "195") (name "unconnected-(JP17-Pad1)") (class "Default")
      (node (ref "JP17") (pin "1") (pinfunction "1_1") (pintype "passive"))
    )
    (net (code "196") (name "unconnected-(JP17-Pad2)") (class "Default")
      (node (ref "JP17") (pin "2") (pinfunction "2_2") (pintype "passive"))
    )
    (net (code "197") (name "unconnected-(JP17-Pad3)") (class "Default")
      (node (ref "JP17") (pin "3") (pinfunction "3_3") (pintype "passive"))
    )
    (net (code "198") (name "unconnected-(JP17-Pad4)") (class "Default")
      (node (ref "JP17") (pin "4") (pinfunction "4_4") (pintype "passive"))
    )
    (net (code "199") (name "unconnected-(JP17-Pad5)") (class "Default")
      (node (ref "JP17") (pin "5") (pinfunction "5_5") (pintype "passive"))
    )
    (net (code "200") (name "unconnected-(JP17-Pad6)") (class "Default")
      (node (ref "JP17") (pin "6") (pinfunction "6_6") (pintype "passive"))
    )
    (net (code "201") (name "unconnected-(JP17-Pad7)") (class "Default")
      (node (ref "JP17") (pin "7") (pinfunction "7_7") (pintype "passive"))
    )
    (net (code "202") (name "unconnected-(JP17-Pad8)") (class "Default")
      (node (ref "JP17") (pin "8") (pinfunction "8_8") (pintype "passive"))
    )
    (net (code "203") (name "unconnected-(JP17-Pad9)") (class "Default")
      (node (ref "JP17") (pin "9") (pinfunction "9_9") (pintype "passive"))
    )
    (net (code "204") (name "unconnected-(JP17-Pad10)") (class "Default")
      (node (ref "JP17") (pin "10") (pinfunction "10_10") (pintype "passive"))
    )
    (net (code "205") (name "unconnected-(JP17-Pad11)") (class "Default")
      (node (ref "JP17") (pin "11") (pinfunction "11_11") (pintype "passive"))
    )
    (net (code "206") (name "unconnected-(JP17-Pad12)") (class "Default")
      (node (ref "JP17") (pin "12") (pinfunction "12_12") (pintype "passive"))
    )
    (net (code "207") (name "unconnected-(U1-PadAREF)") (class "Default")
      (node (ref "U1") (pin "AREF") (pinfunction "AREF_AREF") (pintype "bidirectional"))
    )
    (net (code "208") (name "unconnected-(U1-PadIOREF)") (class "Default")
      (node (ref "U1") (pin "IOREF") (pinfunction "IOREF_IOREF") (pintype "output"))
    )
    (net (code "209") (name "unconnected-(U1-PadRESERVED)") (class "Default")
      (node (ref "U1") (pin "RESERVED") (pinfunction "RESERVED_RESERVED") (pintype "no_connect"))
    )
    (net (code "210") (name "unconnected-(U1-PadSCL)") (class "Default")
      (node (ref "U1") (pin "SCL") (pinfunction "SCL_SCL") (pintype "bidirectional"))
    )
    (net (code "211") (name "unconnected-(U1-PadSDA)") (class "Default")
      (node (ref "U1") (pin "SDA") (pinfunction "SDA_SDA") (pintype "bidirectional"))
    )
  )
)
